# bpod_stepper_1_5_0.net
KiCad netlist of a schematic drawn in EAGLE
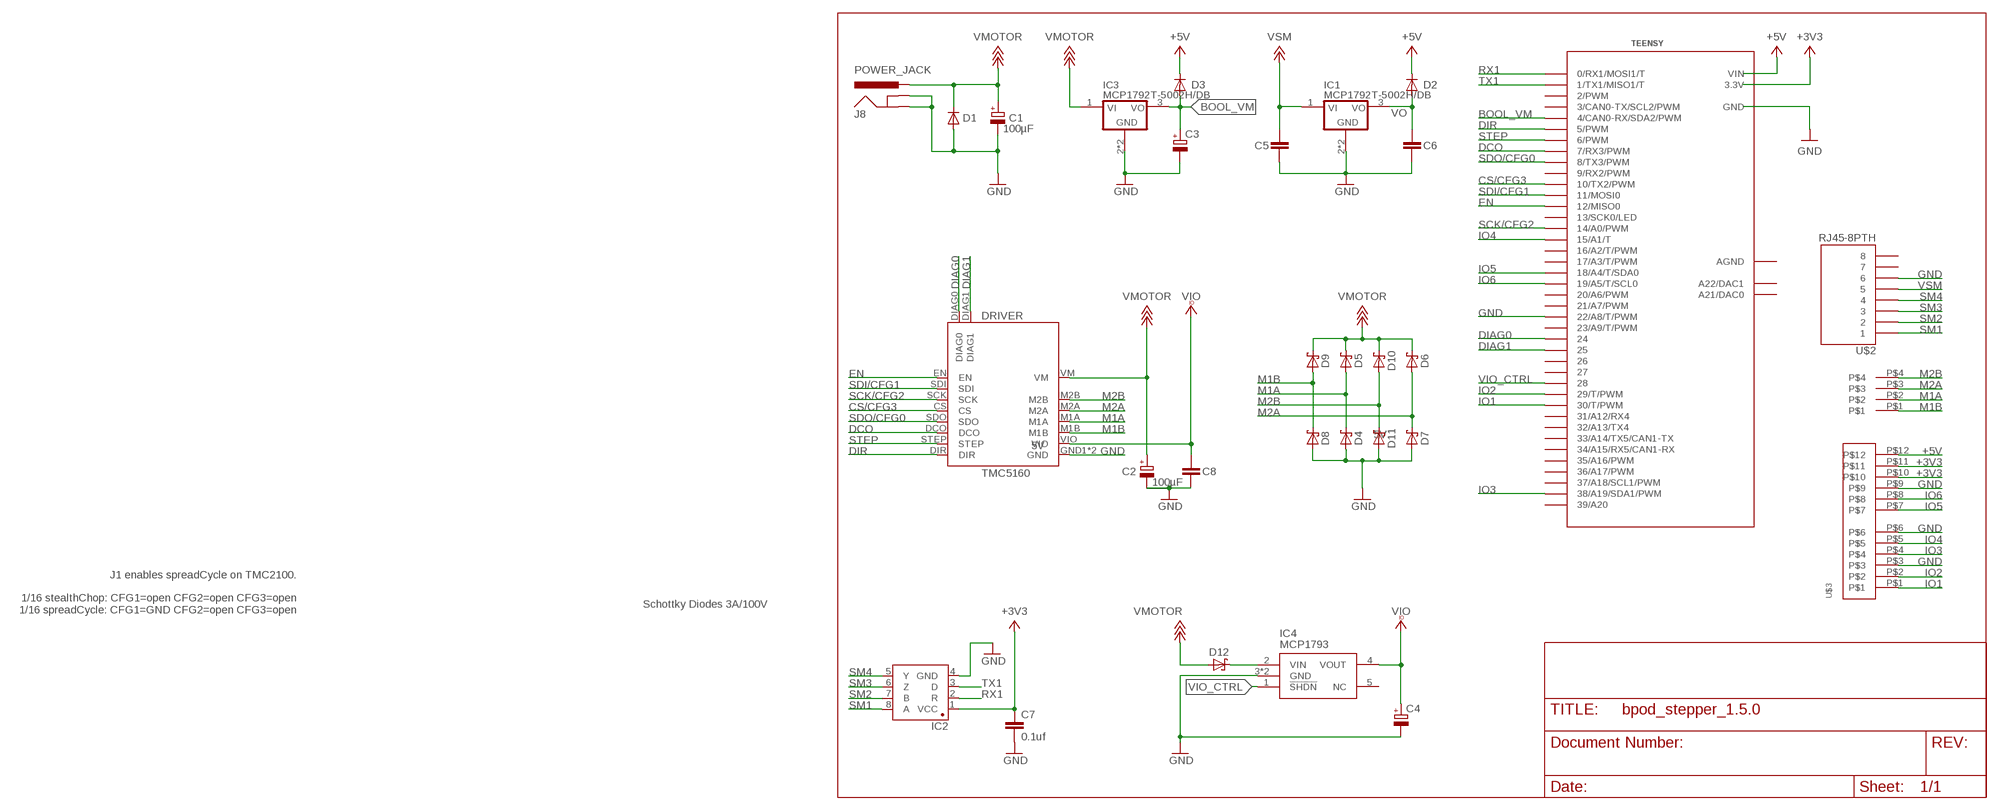
[diagram p0: schematic, sheet 1]

(export (version "E")
  (design (tool "Eeschema 10.0.6"))
  (components
    (comp (ref "C1")
      (value "100µF")
      (footprint "eagle-import:PANASONIC_G")
      (libsource (lib "eagle-import") (part "CPOL-EUG"))
    )
    (comp (ref "C2")
      (value "100µF")
      (footprint "eagle-import:PANASONIC_G")
      (libsource (lib "eagle-import") (part "CPOL-EUG"))
    )
    (comp (ref "C3")
      (value "CPOL-EUB")
      (footprint "eagle-import:PANASONIC_B")
      (libsource (lib "eagle-import") (part "CPOL-EUB"))
    )
    (comp (ref "C4")
      (value "CPOL-EUB")
      (footprint "eagle-import:PANASONIC_B")
      (libsource (lib "eagle-import") (part "CPOL-EUB"))
    )
    (comp (ref "C5")
      (value "0.1uf")
      (footprint "eagle-import:1206@1")
      (libsource (lib "eagle-import") (part "CAP1206"))
    )
    (comp (ref "C6")
      (value "0.1uf")
      (footprint "eagle-import:1206@1")
      (libsource (lib "eagle-import") (part "CAP1206"))
    )
    (comp (ref "C7")
      (value "0.1uf")
      (footprint "eagle-import:1206@1")
      (libsource (lib "eagle-import") (part "CAP1206"))
    )
    (comp (ref "C8")
      (value "100nf")
      (footprint "eagle-import:1206@1")
      (libsource (lib "eagle-import") (part "CAP1206"))
    )
    (comp (ref "D1")
      (value "DIODE-DO214AA")
      (footprint "eagle-import:DO214AA")
      (libsource (lib "eagle-import") (part "DIODE-DO214AA"))
    )
    (comp (ref "D2")
      (value "MBR0520LT")
      (footprint "eagle-import:SOD123")
      (libsource (lib "eagle-import") (part "MBR0520LT"))
    )
    (comp (ref "D3")
      (value "MBR0520LT")
      (footprint "eagle-import:SOD123")
      (libsource (lib "eagle-import") (part "MBR0520LT"))
    )
    (comp (ref "D4")
      (value "S310FA")
      (footprint "eagle-import:SOD123")
      (libsource (lib "eagle-import") (part "D_SCHOTTKY-SOD123"))
    )
    (comp (ref "D5")
      (value "S310FA")
      (footprint "eagle-import:SOD123")
      (libsource (lib "eagle-import") (part "D_SCHOTTKY-SOD123"))
    )
    (comp (ref "D6")
      (value "S310FA")
      (footprint "eagle-import:SOD123")
      (libsource (lib "eagle-import") (part "D_SCHOTTKY-SOD123"))
    )
    (comp (ref "D7")
      (value "S310FA")
      (footprint "eagle-import:SOD123")
      (libsource (lib "eagle-import") (part "D_SCHOTTKY-SOD123"))
    )
    (comp (ref "D8")
      (value "S310FA")
      (footprint "eagle-import:SOD123")
      (libsource (lib "eagle-import") (part "D_SCHOTTKY-SOD123"))
    )
    (comp (ref "D9")
      (value "S310FA")
      (footprint "eagle-import:SOD123")
      (libsource (lib "eagle-import") (part "D_SCHOTTKY-SOD123"))
    )
    (comp (ref "D10")
      (value "S310FA")
      (footprint "eagle-import:SOD123")
      (libsource (lib "eagle-import") (part "D_SCHOTTKY-SOD123"))
    )
    (comp (ref "D11")
      (value "S310FA")
      (footprint "eagle-import:SOD123")
      (libsource (lib "eagle-import") (part "D_SCHOTTKY-SOD123"))
    )
    (comp (ref "D12")
      (value "S310FA")
      (footprint "eagle-import:SOD123")
      (libsource (lib "eagle-import") (part "D_SCHOTTKY-SOD123"))
    )
    (comp (ref "DRIVER")
      (value "TMC5160")
      (footprint "eagle-import:TMC5160")
      (libsource (lib "eagle-import") (part "TMC5160"))
    )
    (comp (ref "IC1")
      (value "MCP1792T-5002H/DB")
      (footprint "eagle-import:SOT223")
      (libsource (lib "eagle-import") (part "MCP1792T-5002H/DB"))
    )
    (comp (ref "IC2")
      (value "SN65HVD31DR")
      (footprint "eagle-import:SO08")
      (libsource (lib "eagle-import") (part "SN65HVD31DR"))
    )
    (comp (ref "IC3")
      (value "MCP1792T-5002H/DB")
      (footprint "eagle-import:SOT223")
      (libsource (lib "eagle-import") (part "MCP1792T-5002H/DB"))
    )
    (comp (ref "IC4")
      (value "MCP1793")
      (footprint "eagle-import:SOT223-5")
      (libsource (lib "eagle-import") (part "MCP1793_SOT223-5"))
    )
    (comp (ref "J8")
      (value "POWER_JACK")
      (footprint "eagle-import:POWER_JACK_PTH")
      (libsource (lib "eagle-import") (part "POWER_JACK"))
    )
    (comp (ref "TEENSY")
      (value "TEENSY_3.6_DIL")
      (footprint "eagle-import:TEENSY_3.6_DIL")
      (libsource (lib "eagle-import") (part "TEENSY_3.6_DIL"))
    )
    (comp (ref "U$2")
      (value "RJ45-8PTH")
      (footprint "eagle-import:RJ45-8")
      (libsource (lib "eagle-import") (part "RJ45-8PTH"))
    )
    (comp (ref "U$3")
      (value "12POS_MOLEX_SOCKET")
      (footprint "eagle-import:12POS_MOLEX_SOCKET")
      (libsource (lib "eagle-import") (part "12POS_MOLEX_SOCKET"))
    )
    (comp (ref "U$4")
      (value "MOLEX395221004")
      (footprint "eagle-import:MOLEX395221004")
      (libsource (lib "eagle-import") (part "MOLEX395221004"))
    )
  )
  (nets
    (net (code "1") (name "+3V3") (class "Default")
      (node (ref "C7") (pin "1") (pinfunction "1_1") (pintype "passive"))
      (node (ref "IC2") (pin "1") (pinfunction "VCC_1") (pintype "bidirectional"))
      (node (ref "TEENSY") (pin "3.3V") (pinfunction "3.3V_3.3V") (pintype "power_in"))
      (node (ref "TEENSY") (pin "3.3V3") (pinfunction "3.3V_3.3V3") (pintype "power_in"))
      (node (ref "U$3") (pin "P$10") (pinfunction "P$10_P$10") (pintype "bidirectional"))
      (node (ref "U$3") (pin "P$11") (pinfunction "P$11_P$11") (pintype "bidirectional"))
    )
    (net (code "2") (name "+5V") (class "Default")
      (node (ref "D2") (pin "C") (pinfunction "C_C") (pintype "passive"))
      (node (ref "D3") (pin "C") (pinfunction "C_C") (pintype "passive"))
      (node (ref "TEENSY") (pin "VIN") (pinfunction "VIN_VIN") (pintype "power_in"))
      (node (ref "U$3") (pin "P$12") (pinfunction "P$12_P$12") (pintype "bidirectional"))
    )
    (net (code "3") (name "+12V") (class "Default")
      (node (ref "C5") (pin "2") (pinfunction "2_2") (pintype "passive"))
      (node (ref "IC1") (pin "1") (pinfunction "VI_1") (pintype "power_in"))
      (node (ref "U$2") (pin "5") (pinfunction "5_5") (pintype "bidirectional"))
    )
    (net (code "4") (name "+18V") (class "Default")
      (node (ref "C1") (pin "+") (pinfunction "+_+") (pintype "passive"))
      (node (ref "C2") (pin "+") (pinfunction "+_+") (pintype "passive"))
      (node (ref "D1") (pin "C") (pinfunction "C_C") (pintype "passive"))
      (node (ref "D10") (pin "C") (pinfunction "C_C") (pintype "passive"))
      (node (ref "D12") (pin "A") (pinfunction "A_A") (pintype "passive"))
      (node (ref "D5") (pin "C") (pinfunction "C_C") (pintype "passive"))
      (node (ref "D6") (pin "C") (pinfunction "C_C") (pintype "passive"))
      (node (ref "D9") (pin "C") (pinfunction "C_C") (pintype "passive"))
      (node (ref "DRIVER") (pin "VM") (pinfunction "VM_VM") (pintype "power_in"))
      (node (ref "IC3") (pin "1") (pinfunction "VI_1") (pintype "power_in"))
      (node (ref "J8") (pin "PWR") (pinfunction "PWR_PWR") (pintype "bidirectional"))
    )
    (net (code "5") (name "/AGND") (class "Default")
      (node (ref "TEENSY") (pin "AGND") (pinfunction "AGND_AGND") (pintype "power_in"))
    )
    (net (code "6") (name "/CS{slash}CFG3") (class "Default")
      (node (ref "DRIVER") (pin "CS") (pinfunction "CS_CS") (pintype "passive"))
      (node (ref "TEENSY") (pin "10") (pinfunction "10/TX2/PWM_10") (pintype "bidirectional"))
    )
    (net (code "7") (name "/DCO") (class "Default")
      (node (ref "DRIVER") (pin "DCO") (pinfunction "DCO_DCO") (pintype "passive"))
      (node (ref "TEENSY") (pin "7") (pinfunction "7/RX3/PWM_7") (pintype "bidirectional"))
    )
    (net (code "8") (name "/DIAG0") (class "Default")
      (node (ref "DRIVER") (pin "DIAG0") (pinfunction "DIAG0_DIAG0") (pintype "passive"))
      (node (ref "TEENSY") (pin "24") (pinfunction "24_24") (pintype "bidirectional"))
    )
    (net (code "9") (name "/DIAG1") (class "Default")
      (node (ref "DRIVER") (pin "DIAG1") (pinfunction "DIAG1_DIAG1") (pintype "passive"))
      (node (ref "TEENSY") (pin "25") (pinfunction "25_25") (pintype "bidirectional"))
    )
    (net (code "10") (name "/DIR") (class "Default")
      (node (ref "DRIVER") (pin "DIR") (pinfunction "DIR_DIR") (pintype "input"))
      (node (ref "TEENSY") (pin "5") (pinfunction "5/PWM_5") (pintype "bidirectional"))
    )
    (net (code "11") (name "/EN") (class "Default")
      (node (ref "DRIVER") (pin "EN") (pinfunction "EN_EN") (pintype "passive"))
      (node (ref "TEENSY") (pin "12") (pinfunction "12/MISO0_12") (pintype "bidirectional"))
    )
    (net (code "12") (name "/IO1") (class "Default")
      (node (ref "TEENSY") (pin "30") (pinfunction "30/T/PWM_30") (pintype "bidirectional"))
      (node (ref "U$3") (pin "P$1") (pinfunction "P$1_P$1") (pintype "bidirectional"))
    )
    (net (code "13") (name "/IO2") (class "Default")
      (node (ref "TEENSY") (pin "29") (pinfunction "29/T/PWM_29") (pintype "bidirectional"))
      (node (ref "U$3") (pin "P$2") (pinfunction "P$2_P$2") (pintype "bidirectional"))
    )
    (net (code "14") (name "/IO3") (class "Default")
      (node (ref "TEENSY") (pin "38/A19") (pinfunction "38/A19/SDA1/PWM_38/A19") (pintype "bidirectional"))
      (node (ref "U$3") (pin "P$4") (pinfunction "P$4_P$4") (pintype "bidirectional"))
    )
    (net (code "15") (name "/IO4") (class "Default")
      (node (ref "TEENSY") (pin "15/A1") (pinfunction "15/A1/T_15/A1") (pintype "bidirectional"))
      (node (ref "U$3") (pin "P$5") (pinfunction "P$5_P$5") (pintype "bidirectional"))
    )
    (net (code "16") (name "/IO5") (class "Default")
      (node (ref "TEENSY") (pin "18/A4") (pinfunction "18/A4/T/SDA0_18/A4") (pintype "bidirectional"))
      (node (ref "U$3") (pin "P$7") (pinfunction "P$7_P$7") (pintype "bidirectional"))
    )
    (net (code "17") (name "/IO6") (class "Default")
      (node (ref "TEENSY") (pin "19/A5") (pinfunction "19/A5/T/SCL0_19/A5") (pintype "bidirectional"))
      (node (ref "U$3") (pin "P$8") (pinfunction "P$8_P$8") (pintype "bidirectional"))
    )
    (net (code "18") (name "/M1A") (class "Default")
      (node (ref "D4") (pin "C") (pinfunction "C_C") (pintype "passive"))
      (node (ref "D5") (pin "A") (pinfunction "A_A") (pintype "passive"))
      (node (ref "DRIVER") (pin "M1A") (pinfunction "M1A_M1A") (pintype "output"))
      (node (ref "U$4") (pin "P$2") (pinfunction "P$2_P$2") (pintype "bidirectional"))
    )
    (net (code "19") (name "/M1B") (class "Default")
      (node (ref "D8") (pin "C") (pinfunction "C_C") (pintype "passive"))
      (node (ref "D9") (pin "A") (pinfunction "A_A") (pintype "passive"))
      (node (ref "DRIVER") (pin "M1B") (pinfunction "M1B_M1B") (pintype "output"))
      (node (ref "U$4") (pin "P$1") (pinfunction "P$1_P$1") (pintype "bidirectional"))
    )
    (net (code "20") (name "/M2A") (class "Default")
      (node (ref "D6") (pin "A") (pinfunction "A_A") (pintype "passive"))
      (node (ref "D7") (pin "C") (pinfunction "C_C") (pintype "passive"))
      (node (ref "DRIVER") (pin "M2A") (pinfunction "M2A_M2A") (pintype "output"))
      (node (ref "U$4") (pin "P$3") (pinfunction "P$3_P$3") (pintype "bidirectional"))
    )
    (net (code "21") (name "/M2B") (class "Default")
      (node (ref "D10") (pin "A") (pinfunction "A_A") (pintype "passive"))
      (node (ref "D11") (pin "C") (pinfunction "C_C") (pintype "passive"))
      (node (ref "DRIVER") (pin "M2B") (pinfunction "M2B_M2B") (pintype "output"))
      (node (ref "U$4") (pin "P$4") (pinfunction "P$4_P$4") (pintype "bidirectional"))
    )
    (net (code "22") (name "/RX1") (class "Default")
      (node (ref "IC2") (pin "2") (pinfunction "R_2") (pintype "bidirectional"))
      (node (ref "TEENSY") (pin "0") (pinfunction "0/RX1/MOSI1/T_0") (pintype "bidirectional"))
    )
    (net (code "23") (name "/SCK{slash}CFG2") (class "Default")
      (node (ref "DRIVER") (pin "SCK") (pinfunction "SCK_SCK") (pintype "passive"))
      (node (ref "TEENSY") (pin "14/A0") (pinfunction "14/A0/PWM_14/A0") (pintype "bidirectional"))
    )
    (net (code "24") (name "/SDI{slash}CFG1") (class "Default")
      (node (ref "DRIVER") (pin "SDI") (pinfunction "SDI_SDI") (pintype "passive"))
      (node (ref "TEENSY") (pin "11") (pinfunction "11/MOSI0_11") (pintype "bidirectional"))
    )
    (net (code "25") (name "/SDO{slash}CFG0") (class "Default")
      (node (ref "DRIVER") (pin "SDO") (pinfunction "SDO_SDO") (pintype "passive"))
      (node (ref "TEENSY") (pin "8") (pinfunction "8/TX3/PWM_8") (pintype "bidirectional"))
    )
    (net (code "26") (name "/SM1") (class "Default")
      (node (ref "IC2") (pin "8") (pinfunction "A_8") (pintype "bidirectional"))
      (node (ref "U$2") (pin "1") (pinfunction "1_1") (pintype "bidirectional"))
    )
    (net (code "27") (name "/SM2") (class "Default")
      (node (ref "IC2") (pin "7") (pinfunction "B_7") (pintype "bidirectional"))
      (node (ref "U$2") (pin "2") (pinfunction "2_2") (pintype "bidirectional"))
    )
    (net (code "28") (name "/SM3") (class "Default")
      (node (ref "IC2") (pin "6") (pinfunction "Z_6") (pintype "bidirectional"))
      (node (ref "U$2") (pin "3") (pinfunction "3_3") (pintype "bidirectional"))
    )
    (net (code "29") (name "/SM4") (class "Default")
      (node (ref "IC2") (pin "5") (pinfunction "Y_5") (pintype "bidirectional"))
      (node (ref "U$2") (pin "4") (pinfunction "4_4") (pintype "bidirectional"))
    )
    (net (code "30") (name "/STEP") (class "Default")
      (node (ref "DRIVER") (pin "STEP") (pinfunction "STEP_STEP") (pintype "input"))
      (node (ref "TEENSY") (pin "6") (pinfunction "6/PWM_6") (pintype "bidirectional"))
    )
    (net (code "31") (name "/TX1") (class "Default")
      (node (ref "IC2") (pin "3") (pinfunction "D_3") (pintype "bidirectional"))
      (node (ref "TEENSY") (pin "1") (pinfunction "1/TX1/MISO1/T_1") (pintype "bidirectional"))
    )
    (net (code "32") (name "/VO") (class "Default")
      (node (ref "C6") (pin "2") (pinfunction "2_2") (pintype "passive"))
      (node (ref "D2") (pin "A") (pinfunction "A_A") (pintype "passive"))
      (node (ref "IC1") (pin "3") (pinfunction "VO_3") (pintype "passive"))
    )
    (net (code "33") (name "BOOL_VM") (class "Default")
      (node (ref "C3") (pin "+") (pinfunction "+_+") (pintype "passive"))
      (node (ref "D3") (pin "A") (pinfunction "A_A") (pintype "passive"))
      (node (ref "IC3") (pin "3") (pinfunction "VO_3") (pintype "passive"))
      (node (ref "TEENSY") (pin "4") (pinfunction "4/CAN0-RX/SDA2/PWM_4") (pintype "bidirectional"))
    )
    (net (code "34") (name "GND") (class "Default")
      (node (ref "C1") (pin "-") (pinfunction "-_-") (pintype "passive"))
      (node (ref "C2") (pin "-") (pinfunction "-_-") (pintype "passive"))
      (node (ref "C3") (pin "-") (pinfunction "-_-") (pintype "passive"))
      (node (ref "C4") (pin "-") (pinfunction "-_-") (pintype "passive"))
      (node (ref "C5") (pin "1") (pinfunction "1_1") (pintype "passive"))
      (node (ref "C6") (pin "1") (pinfunction "1_1") (pintype "passive"))
      (node (ref "C7") (pin "2") (pinfunction "2_2") (pintype "passive"))
      (node (ref "C8") (pin "2") (pinfunction "2_2") (pintype "passive"))
      (node (ref "D1") (pin "A") (pinfunction "A_A") (pintype "passive"))
      (node (ref "D11") (pin "A") (pinfunction "A_A") (pintype "passive"))
      (node (ref "D4") (pin "A") (pinfunction "A_A") (pintype "passive"))
      (node (ref "D7") (pin "A") (pinfunction "A_A") (pintype "passive"))
      (node (ref "D8") (pin "A") (pinfunction "A_A") (pintype "passive"))
      (node (ref "DRIVER") (pin "GND1") (pinfunction "GND_GND1") (pintype "power_in"))
      (node (ref "DRIVER") (pin "GND2") (pinfunction "GND_GND2") (pintype "power_in"))
      (node (ref "IC1") (pin "2") (pinfunction "GND_2") (pintype "power_in"))
      (node (ref "IC1") (pin "4") (pinfunction "GND_4") (pintype "power_in"))
      (node (ref "IC2") (pin "4") (pinfunction "GND_4") (pintype "bidirectional"))
      (node (ref "IC3") (pin "2") (pinfunction "GND_2") (pintype "power_in"))
      (node (ref "IC3") (pin "4") (pinfunction "GND_4") (pintype "power_in"))
      (node (ref "IC4") (pin "3") (pinfunction "GND_3") (pintype "bidirectional"))
      (node (ref "IC4") (pin "6") (pinfunction "GND_6") (pintype "bidirectional"))
      (node (ref "J8") (pin "GND") (pinfunction "GND_GND") (pintype "bidirectional"))
      (node (ref "J8") (pin "GNDBREAK") (pinfunction "GNDBREAK_GNDBREAK") (pintype "bidirectional"))
      (node (ref "TEENSY") (pin "22/A8") (pinfunction "22/A8/T/PWM_22/A8") (pintype "bidirectional"))
      (node (ref "TEENSY") (pin "GND") (pinfunction "GND_GND") (pintype "power_in"))
      (node (ref "TEENSY") (pin "GND1") (pinfunction "GND_GND1") (pintype "power_in"))
      (node (ref "U$2") (pin "6") (pinfunction "6_6") (pintype "bidirectional"))
      (node (ref "U$3") (pin "P$3") (pinfunction "P$3_P$3") (pintype "bidirectional"))
      (node (ref "U$3") (pin "P$6") (pinfunction "P$6_P$6") (pintype "bidirectional"))
      (node (ref "U$3") (pin "P$9") (pinfunction "P$9_P$9") (pintype "bidirectional"))
    )
    (net (code "35") (name "Net-(IC4-VIN)") (class "Default")
      (node (ref "D12") (pin "C") (pinfunction "C_C") (pintype "passive"))
      (node (ref "IC4") (pin "2") (pinfunction "VIN_2") (pintype "bidirectional"))
    )
    (net (code "36") (name "VCCIO") (class "Default")
      (node (ref "C4") (pin "+") (pinfunction "+_+") (pintype "passive"))
      (node (ref "C8") (pin "1") (pinfunction "1_1") (pintype "passive"))
      (node (ref "DRIVER") (pin "VIO") (pinfunction "VIO_VIO") (pintype "power_in"))
      (node (ref "IC4") (pin "4") (pinfunction "VOUT_4") (pintype "bidirectional"))
    )
    (net (code "37") (name "VIO_CTRL") (class "Default")
      (node (ref "IC4") (pin "1") (pinfunction "~{SHDN}_1") (pintype "bidirectional"))
      (node (ref "TEENSY") (pin "28") (pinfunction "28_28") (pintype "bidirectional"))
    )
    (net (code "38") (name "unconnected-(IC4-NC-Pad5)") (class "Default")
      (node (ref "IC4") (pin "5") (pinfunction "NC_5") (pintype "bidirectional"))
    )
    (net (code "39") (name "unconnected-(TEENSY-2{slash}PWM-Pad2)") (class "Default")
      (node (ref "TEENSY") (pin "2") (pinfunction "2/PWM_2") (pintype "bidirectional"))
    )
    (net (code "40") (name "unconnected-(TEENSY-3{slash}CAN0-TX{slash}SCL2{slash}PWM-Pad3)") (class "Default")
      (node (ref "TEENSY") (pin "3") (pinfunction "3/CAN0-TX/SCL2/PWM_3") (pintype "bidirectional"))
    )
    (net (code "41") (name "unconnected-(TEENSY-9{slash}RX2{slash}PWM-Pad9)") (class "Default")
      (node (ref "TEENSY") (pin "9") (pinfunction "9/RX2/PWM_9") (pintype "bidirectional"))
    )
    (net (code "42") (name "unconnected-(TEENSY-13{slash}SCK0{slash}LED-Pad13)") (class "Default")
      (node (ref "TEENSY") (pin "13") (pinfunction "13/SCK0/LED_13") (pintype "bidirectional"))
    )
    (net (code "43") (name "unconnected-(TEENSY-16{slash}A2{slash}T{slash}PWM-Pad16{slash}A2)") (class "Default")
      (node (ref "TEENSY") (pin "16/A2") (pinfunction "16/A2/T/PWM_16/A2") (pintype "bidirectional"))
    )
    (net (code "44") (name "unconnected-(TEENSY-17{slash}A3{slash}T{slash}PWM-Pad17{slash}A3)") (class "Default")
      (node (ref "TEENSY") (pin "17/A3") (pinfunction "17/A3/T/PWM_17/A3") (pintype "bidirectional"))
    )
    (net (code "45") (name "unconnected-(TEENSY-20{slash}A6{slash}PWM-Pad20{slash}A6)") (class "Default")
      (node (ref "TEENSY") (pin "20/A6") (pinfunction "20/A6/PWM_20/A6") (pintype "bidirectional"))
    )
    (net (code "46") (name "unconnected-(TEENSY-21{slash}A7{slash}PWM-Pad21{slash}A7)") (class "Default")
      (node (ref "TEENSY") (pin "21/A7") (pinfunction "21/A7/PWM_21/A7") (pintype "bidirectional"))
    )
    (net (code "47") (name "unconnected-(TEENSY-23{slash}A9{slash}T{slash}PWM-Pad23{slash}A9)") (class "Default")
      (node (ref "TEENSY") (pin "23/A9") (pinfunction "23/A9/T/PWM_23/A9") (pintype "bidirectional"))
    )
    (net (code "48") (name "unconnected-(TEENSY-31{slash}A12{slash}RX4-Pad31{slash}A12)") (class "Default")
      (node (ref "TEENSY") (pin "31/A12") (pinfunction "31/A12/RX4_31/A12") (pintype "bidirectional"))
    )
    (net (code "49") (name "unconnected-(TEENSY-32{slash}A13{slash}TX4-Pad32{slash}A13)") (class "Default")
      (node (ref "TEENSY") (pin "32/A13") (pinfunction "32/A13/TX4_32/A13") (pintype "bidirectional"))
    )
    (net (code "50") (name "unconnected-(TEENSY-33{slash}A14{slash}TX5{slash}CAN1-TX-Pad33{slash}A14)") (class "Default")
      (node (ref "TEENSY") (pin "33/A14") (pinfunction "33/A14/TX5/CAN1-TX_33/A14") (pintype "bidirectional"))
    )
    (net (code "51") (name "unconnected-(TEENSY-34{slash}A15{slash}RX5{slash}CAN1-RX-Pad34{slash}A15)") (class "Default")
      (node (ref "TEENSY") (pin "34/A15") (pinfunction "34/A15/RX5/CAN1-RX_34/A15") (pintype "bidirectional"))
    )
    (net (code "52") (name "unconnected-(TEENSY-35{slash}A16{slash}PWM-Pad35{slash}A16)") (class "Default")
      (node (ref "TEENSY") (pin "35/A16") (pinfunction "35/A16/PWM_35/A16") (pintype "bidirectional"))
    )
    (net (code "53") (name "unconnected-(TEENSY-36{slash}A17{slash}PWM-Pad36{slash}A17)") (class "Default")
      (node (ref "TEENSY") (pin "36/A17") (pinfunction "36/A17/PWM_36/A17") (pintype "bidirectional"))
    )
    (net (code "54") (name "unconnected-(TEENSY-37{slash}A18{slash}SCL1{slash}PWM-Pad37{slash}A18)") (class "Default")
      (node (ref "TEENSY") (pin "37/A18") (pinfunction "37/A18/SCL1/PWM_37/A18") (pintype "bidirectional"))
    )
    (net (code "55") (name "unconnected-(TEENSY-A21{slash}DAC0-PadA21)") (class "Default")
      (node (ref "TEENSY") (pin "A21") (pinfunction "A21/DAC0_A21") (pintype "bidirectional"))
    )
    (net (code "56") (name "unconnected-(TEENSY-A22{slash}DAC1-PadA22)") (class "Default")
      (node (ref "TEENSY") (pin "A22") (pinfunction "A22/DAC1_A22") (pintype "bidirectional"))
    )
    (net (code "57") (name "unconnected-(TEENSY-Pad26)") (class "Default")
      (node (ref "TEENSY") (pin "26") (pinfunction "26_26") (pintype "bidirectional"))
    )
    (net (code "58") (name "unconnected-(TEENSY-Pad27)") (class "Default")
      (node (ref "TEENSY") (pin "27") (pinfunction "27_27") (pintype "bidirectional"))
    )
    (net (code "59") (name "unconnected-(TEENSY-Pad39{slash}A20)") (class "Default")
      (node (ref "TEENSY") (pin "39/A20") (pinfunction "39/A20_39/A20") (pintype "bidirectional"))
    )
    (net (code "60") (name "unconnected-(U$2-Pad7)") (class "Default")
      (node (ref "U$2") (pin "7") (pinfunction "7_7") (pintype "bidirectional"))
    )
    (net (code "61") (name "unconnected-(U$2-Pad8)") (class "Default")
      (node (ref "U$2") (pin "8") (pinfunction "8_8") (pintype "bidirectional"))
    )
  )
)
